# STlinkv21.net
KiCad netlist of a schematic drawn in Altium Designer
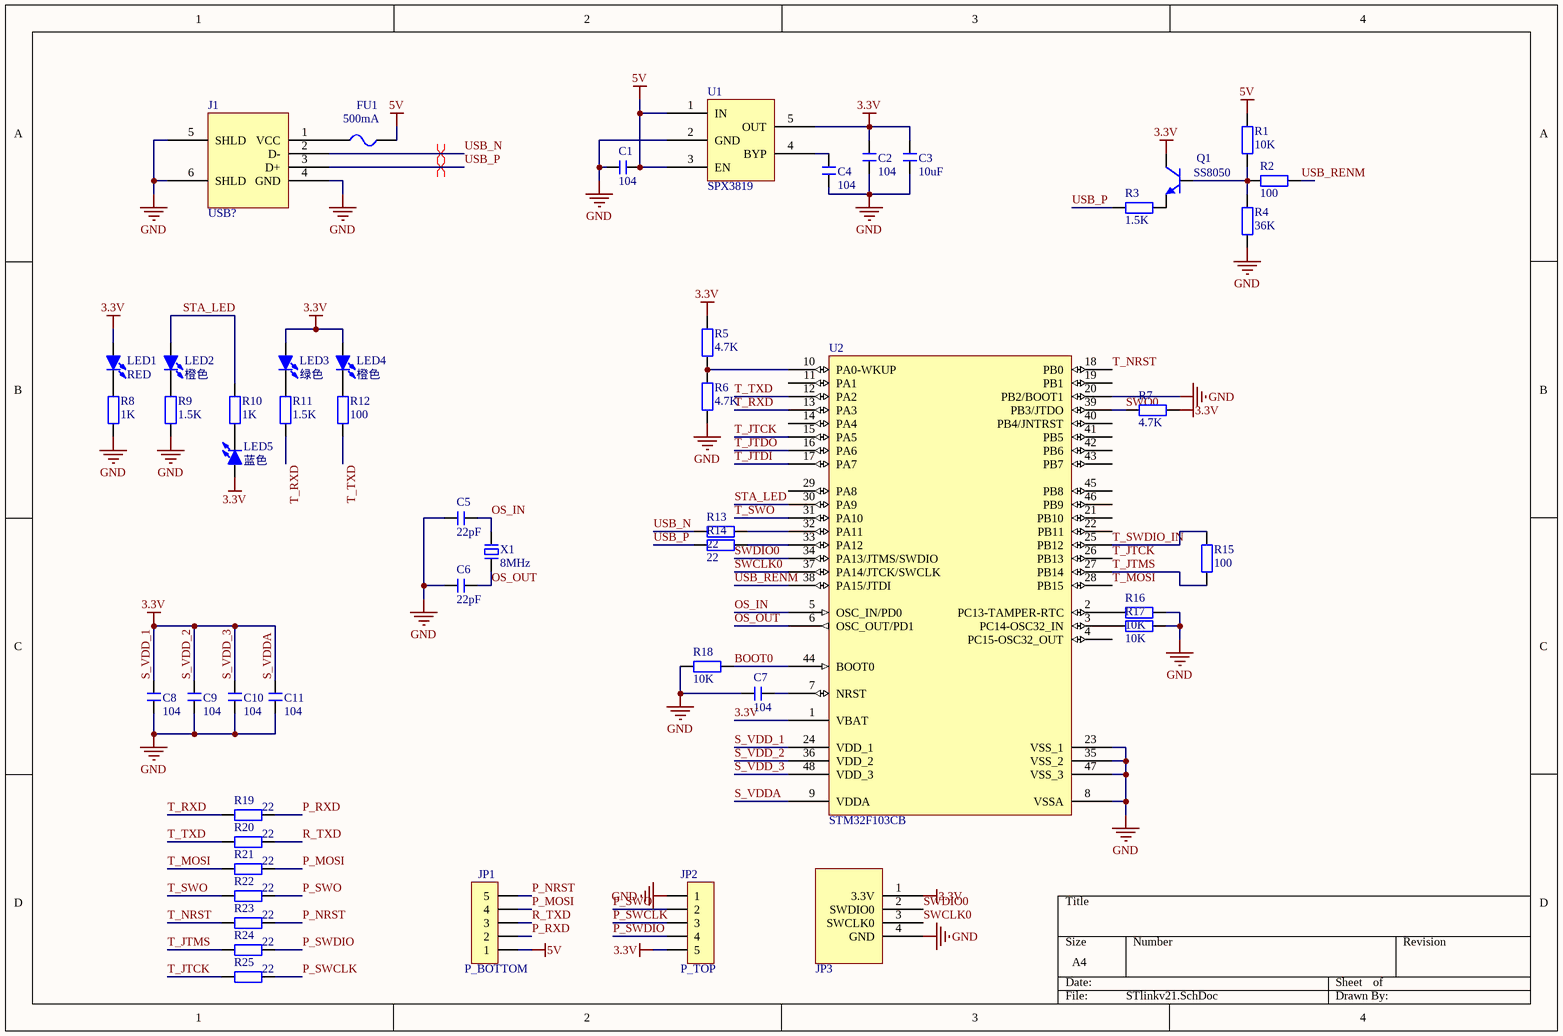
[diagram p0: STlinkv21.SchDoc]

(export (version "E")
  (design (tool "Eeschema 10.0.6"))
  (components
    (comp (ref "*") (value "JP3") (footprint "JP4") (libsource (lib "STlinkv21") (part "JP?")))
    (comp (ref "C1")
      (value "104")
      (footprint "C 0603_L")
      (description "无极性贴片电容")
      (fields (field (name "版权归属") "源创客"))
      (libsource (lib "3.1   - 电阻-电容-电感") (part "C"))
    )
    (comp (ref "C2")
      (value "104")
      (footprint "C 0603_L")
      (description "无极性贴片电容")
      (fields (field (name "版权归属") "源创客"))
      (libsource (lib "3.1   - 电阻-电容-电感") (part "C"))
    )
    (comp (ref "C3")
      (value "10uF")
      (footprint "C 0603_L")
      (description "无极性贴片电容")
      (fields (field (name "版权归属") "源创客"))
      (libsource (lib "3.1   - 电阻-电容-电感") (part "C"))
    )
    (comp (ref "C4")
      (value "104")
      (footprint "C 0603_L")
      (description "无极性贴片电容")
      (fields (field (name "版权归属") "源创客"))
      (libsource (lib "3.1   - 电阻-电容-电感") (part "C"))
    )
    (comp (ref "C5")
      (value "22pF")
      (footprint "C 0603_L")
      (description "无极性贴片电容")
      (fields (field (name "版权归属") "源创客"))
      (libsource (lib "3.1   - 电阻-电容-电感") (part "C"))
    )
    (comp (ref "C6")
      (value "22pF")
      (footprint "C 0603_L")
      (description "无极性贴片电容")
      (fields (field (name "版权归属") "源创客"))
      (libsource (lib "3.1   - 电阻-电容-电感") (part "C"))
    )
    (comp (ref "C7")
      (value "104")
      (footprint "C 0603_L")
      (description "无极性贴片电容")
      (fields (field (name "版权归属") "源创客"))
      (libsource (lib "3.1   - 电阻-电容-电感") (part "C"))
    )
    (comp (ref "C8")
      (value "104")
      (footprint "C 0603_L")
      (description "无极性贴片电容")
      (fields (field (name "版权归属") "源创客"))
      (libsource (lib "3.1   - 电阻-电容-电感") (part "C"))
    )
    (comp (ref "C9")
      (value "104")
      (footprint "C 0603_L")
      (description "无极性贴片电容")
      (fields (field (name "版权归属") "源创客"))
      (libsource (lib "3.1   - 电阻-电容-电感") (part "C"))
    )
    (comp (ref "C10")
      (value "104")
      (footprint "C 0603_L")
      (description "无极性贴片电容")
      (fields (field (name "版权归属") "源创客"))
      (libsource (lib "3.1   - 电阻-电容-电感") (part "C"))
    )
    (comp (ref "C11")
      (value "104")
      (footprint "C 0603_L")
      (description "无极性贴片电容")
      (fields (field (name "版权归属") "源创客"))
      (libsource (lib "3.1   - 电阻-电容-电感") (part "C"))
    )
    (comp (ref "FU1")
      (value "500mA")
      (footprint "FU 0805")
      (description "贴片保险丝")
      (fields (field (name "版权归属") "源创客"))
      (libsource (lib "10.1 - 保险丝-晶振") (part "FU"))
    )
    (comp (ref "J1") (value "USB?") (footprint "USB-A") (libsource (lib "STlinkv21") (part "USB?")))
    (comp (ref "JP1")
      (value "P_BOTTOM")
      (footprint "JP5Bottom")
      (description "5P接插件")
      (fields (field (name "版权归属") "源创客"))
      (libsource (lib "4.5   - 接插件-脚距2.54") (part "Header 5"))
    )
    (comp (ref "JP2")
      (value "P_TOP")
      (footprint "JP5TOP")
      (description "5P接插件")
      (fields (field (name "版权归属") "源创客"))
      (libsource (lib "") (part "Header 5_1"))
    )
    (comp (ref "LED1")
      (value "RED")
      (footprint "LED 0603B")
      (description "贴片LED")
      (fields (field (name "版权归属") "源创客"))
      (libsource (lib "9.1   - LED") (part "LED-SMD"))
    )
    (comp (ref "LED2")
      (value "橙色")
      (footprint "LED 0603B")
      (description "贴片LED")
      (fields (field (name "版权归属") "源创客"))
      (libsource (lib "9.1   - LED") (part "LED-SMD"))
    )
    (comp (ref "LED3")
      (value "绿色")
      (footprint "LED 0603B")
      (description "贴片LED")
      (fields (field (name "版权归属") "源创客"))
      (libsource (lib "9.1   - LED") (part "LED-SMD"))
    )
    (comp (ref "LED4")
      (value "橙色")
      (footprint "LED 0603B")
      (description "贴片LED")
      (fields (field (name "版权归属") "源创客"))
      (libsource (lib "9.1   - LED") (part "LED-SMD"))
    )
    (comp (ref "LED5")
      (value "蓝色")
      (footprint "LED 0603B")
      (description "贴片LED")
      (fields (field (name "版权归属") "源创客"))
      (libsource (lib "9.1   - LED") (part "LED-SMD"))
    )
    (comp (ref "Q1")
      (value "SS8050")
      (footprint "SOT23-3N")
      (description "高频放大-NPN型")
      (fields (field (name "版权归属") "源创客"))
      (libsource (lib "6.2   - 三极管") (part "8050-SMD"))
    )
    (comp (ref "R1")
      (value "10K")
      (footprint "R 0603_L")
      (description "贴片电阻")
      (fields (field (name "版权归属") "源创客"))
      (libsource (lib "3.1   - 电阻-电容-电感") (part "R"))
    )
    (comp (ref "R2")
      (value "100")
      (footprint "R 0603_L")
      (description "贴片电阻")
      (fields (field (name "版权归属") "源创客"))
      (libsource (lib "3.1   - 电阻-电容-电感") (part "R"))
    )
    (comp (ref "R3")
      (value "1.5K")
      (footprint "R 0603_L")
      (description "贴片电阻")
      (fields (field (name "版权归属") "源创客"))
      (libsource (lib "3.1   - 电阻-电容-电感") (part "R"))
    )
    (comp (ref "R4")
      (value "36K")
      (footprint "R 0603_L")
      (description "贴片电阻")
      (fields (field (name "版权归属") "源创客"))
      (libsource (lib "3.1   - 电阻-电容-电感") (part "R"))
    )
    (comp (ref "R5")
      (value "4.7K")
      (footprint "R 0603_L")
      (description "贴片电阻")
      (fields (field (name "版权归属") "源创客"))
      (libsource (lib "3.1   - 电阻-电容-电感") (part "R"))
    )
    (comp (ref "R6")
      (value "4.7K")
      (footprint "R 0603_L")
      (description "贴片电阻")
      (fields (field (name "版权归属") "源创客"))
      (libsource (lib "3.1   - 电阻-电容-电感") (part "R"))
    )
    (comp (ref "R7")
      (value "4.7K")
      (footprint "R 0603_L")
      (description "贴片电阻")
      (fields (field (name "版权归属") "源创客"))
      (libsource (lib "3.1   - 电阻-电容-电感") (part "R"))
    )
    (comp (ref "R8")
      (value "1K")
      (footprint "R 0603_L")
      (description "贴片电阻")
      (fields (field (name "版权归属") "源创客"))
      (libsource (lib "3.1   - 电阻-电容-电感") (part "R"))
    )
    (comp (ref "R9")
      (value "1.5K")
      (footprint "R 0603_L")
      (description "贴片电阻")
      (fields (field (name "版权归属") "源创客"))
      (libsource (lib "3.1   - 电阻-电容-电感") (part "R"))
    )
    (comp (ref "R10")
      (value "1K")
      (footprint "R 0603_L")
      (description "贴片电阻")
      (fields (field (name "版权归属") "源创客"))
      (libsource (lib "3.1   - 电阻-电容-电感") (part "R"))
    )
    (comp (ref "R11")
      (value "1.5K")
      (footprint "R 0603_L")
      (description "贴片电阻")
      (fields (field (name "版权归属") "源创客"))
      (libsource (lib "3.1   - 电阻-电容-电感") (part "R"))
    )
    (comp (ref "R12")
      (value "100")
      (footprint "R 0603_L")
      (description "贴片电阻")
      (fields (field (name "版权归属") "源创客"))
      (libsource (lib "3.1   - 电阻-电容-电感") (part "R"))
    )
    (comp (ref "R13")
      (value "22")
      (footprint "R 0603_L")
      (description "贴片电阻")
      (fields (field (name "版权归属") "源创客"))
      (libsource (lib "3.1   - 电阻-电容-电感") (part "R"))
    )
    (comp (ref "R14")
      (value "22")
      (footprint "R 0603_L")
      (description "贴片电阻")
      (fields (field (name "版权归属") "源创客"))
      (libsource (lib "3.1   - 电阻-电容-电感") (part "R"))
    )
    (comp (ref "R15")
      (value "100")
      (footprint "R 0603_L")
      (description "贴片电阻")
      (fields (field (name "版权归属") "源创客"))
      (libsource (lib "3.1   - 电阻-电容-电感") (part "R"))
    )
    (comp (ref "R16")
      (value "10K")
      (footprint "R 0603_L")
      (description "贴片电阻")
      (fields (field (name "版权归属") "源创客"))
      (libsource (lib "3.1   - 电阻-电容-电感") (part "R"))
    )
    (comp (ref "R17")
      (value "10K")
      (footprint "R 0603_L")
      (description "贴片电阻")
      (fields (field (name "版权归属") "源创客"))
      (libsource (lib "3.1   - 电阻-电容-电感") (part "R"))
    )
    (comp (ref "R18")
      (value "10K")
      (footprint "R 0603_L")
      (description "贴片电阻")
      (fields (field (name "版权归属") "源创客"))
      (libsource (lib "3.1   - 电阻-电容-电感") (part "R"))
    )
    (comp (ref "R19")
      (value "22")
      (footprint "R 0603_L")
      (description "贴片电阻")
      (fields (field (name "版权归属") "源创客"))
      (libsource (lib "3.1   - 电阻-电容-电感") (part "R"))
    )
    (comp (ref "R20")
      (value "22")
      (footprint "R 0603_L")
      (description "贴片电阻")
      (fields (field (name "版权归属") "源创客"))
      (libsource (lib "3.1   - 电阻-电容-电感") (part "R"))
    )
    (comp (ref "R21")
      (value "22")
      (footprint "R 0603_L")
      (description "贴片电阻")
      (fields (field (name "版权归属") "源创客"))
      (libsource (lib "3.1   - 电阻-电容-电感") (part "R"))
    )
    (comp (ref "R22")
      (value "22")
      (footprint "R 0603_L")
      (description "贴片电阻")
      (fields (field (name "版权归属") "源创客"))
      (libsource (lib "3.1   - 电阻-电容-电感") (part "R"))
    )
    (comp (ref "R23")
      (value "22")
      (footprint "R 0603_L")
      (description "贴片电阻")
      (fields (field (name "版权归属") "源创客"))
      (libsource (lib "3.1   - 电阻-电容-电感") (part "R"))
    )
    (comp (ref "R24")
      (value "22")
      (footprint "R 0603_L")
      (description "贴片电阻")
      (fields (field (name "版权归属") "源创客"))
      (libsource (lib "3.1   - 电阻-电容-电感") (part "R"))
    )
    (comp (ref "R25")
      (value "22")
      (footprint "R 0603_L")
      (description "贴片电阻")
      (fields (field (name "版权归属") "源创客"))
      (libsource (lib "3.1   - 电阻-电容-电感") (part "R"))
    )
    (comp (ref "U1") (value "SPX3819") (footprint "SOT-23-5") (libsource (lib "STlinkv21") (part "SPX3819")))
    (comp (ref "U2")
      (value "STM32F103CB")
      (footprint "LQFP48 7X7_L")
      (description "Flaah:64/RAM:20/IO:36")
      (fields (field (name "版权归属") "源创客"))
      (libsource (lib "2.1   - STM32系列单片机") (part "STM32F103C8"))
    )
    (comp (ref "X1")
      (value "8MHz")
      (footprint "OSC 5032-2P")
      (description "2脚无源脚晶振")
      (fields (field (name "版权归属") "源创客"))
      (libsource (lib "10.1 - 保险丝-晶振") (part "XTAL-2P"))
    )
  )
  (nets
    (net (code "1") (name "/BOOT0") (class "Default")
      (node (ref "R18") (pin "1") (pinfunction "1_1") (pintype "passive"))
      (node (ref "U2") (pin "44") (pinfunction "BOOT0_44") (pintype "input"))
    )
    (net (code "2") (name "/OS_IN") (class "Default")
      (node (ref "C5") (pin "2") (pinfunction "2_2") (pintype "passive"))
      (node (ref "U2") (pin "5") (pinfunction "OSC_IN/PD0_5") (pintype "input"))
      (node (ref "X1") (pin "2") (pinfunction "2_2") (pintype "passive"))
    )
    (net (code "3") (name "/OS_OUT") (class "Default")
      (node (ref "C6") (pin "2") (pinfunction "2_2") (pintype "passive"))
      (node (ref "U2") (pin "6") (pinfunction "OSC_OUT/PD1_6") (pintype "output"))
      (node (ref "X1") (pin "1") (pinfunction "1_1") (pintype "passive"))
    )
    (net (code "4") (name "/P_MOSI") (class "Default")
      (node (ref "JP1") (pin "4") (pinfunction "4_4") (pintype "passive"))
      (node (ref "R21") (pin "1") (pinfunction "1_1") (pintype "passive"))
    )
    (net (code "5") (name "/P_NRST") (class "Default")
      (node (ref "JP1") (pin "5") (pinfunction "5_5") (pintype "passive"))
      (node (ref "R23") (pin "1") (pinfunction "1_1") (pintype "passive"))
    )
    (net (code "6") (name "/P_RXD") (class "Default")
      (node (ref "JP1") (pin "2") (pinfunction "2_2") (pintype "passive"))
      (node (ref "R19") (pin "1") (pinfunction "1_1") (pintype "passive"))
    )
    (net (code "7") (name "/P_SWCLK") (class "Default")
      (node (ref "JP2") (pin "3") (pinfunction "3_3") (pintype "passive"))
      (node (ref "R25") (pin "1") (pinfunction "1_1") (pintype "passive"))
    )
    (net (code "8") (name "/P_SWDIO") (class "Default")
      (node (ref "JP2") (pin "4") (pinfunction "4_4") (pintype "passive"))
      (node (ref "R24") (pin "1") (pinfunction "1_1") (pintype "passive"))
    )
    (net (code "9") (name "/P_SWO") (class "Default")
      (node (ref "JP2") (pin "2") (pinfunction "2_2") (pintype "passive"))
      (node (ref "R22") (pin "1") (pinfunction "1_1") (pintype "passive"))
    )
    (net (code "10") (name "/R_TXD") (class "Default")
      (node (ref "JP1") (pin "3") (pinfunction "3_3") (pintype "passive"))
      (node (ref "R20") (pin "1") (pinfunction "1_1") (pintype "passive"))
    )
    (net (code "11") (name "/STA_LED") (class "Default")
      (node (ref "LED2") (pin "1") (pinfunction "A_1") (pintype "passive"))
      (node (ref "R10") (pin "2") (pinfunction "2_2") (pintype "passive"))
      (node (ref "U2") (pin "30") (pinfunction "PA9_30") (pintype "bidirectional"))
    )
    (net (code "12") (name "/SWCLK0") (class "Default")
      (node (ref "*") (pin "3") (pinfunction "SWCLK0_3") (pintype "passive"))
      (node (ref "U2") (pin "37") (pinfunction "PA14/JTCK/SWCLK_37") (pintype "bidirectional"))
    )
    (net (code "13") (name "/SWDIO0") (class "Default")
      (node (ref "*") (pin "2") (pinfunction "SWDIO0_2") (pintype "passive"))
      (node (ref "U2") (pin "34") (pinfunction "PA13/JTMS/SWDIO_34") (pintype "bidirectional"))
    )
    (net (code "14") (name "/SWO0") (class "Default")
      (node (ref "R7") (pin "1") (pinfunction "1_1") (pintype "passive"))
      (node (ref "U2") (pin "39") (pinfunction "PB3/JTDO_39") (pintype "bidirectional"))
    )
    (net (code "15") (name "/T_JTCK") (class "Default")
      (node (ref "R25") (pin "2") (pinfunction "2_2") (pintype "passive"))
      (node (ref "U2") (pin "15") (pinfunction "PA5_15") (pintype "bidirectional"))
      (node (ref "U2") (pin "26") (pinfunction "PB13_26") (pintype "bidirectional"))
    )
    (net (code "16") (name "/T_JTDI") (class "Default")
      (node (ref "U2") (pin "17") (pinfunction "PA7_17") (pintype "bidirectional"))
    )
    (net (code "17") (name "/T_JTDO") (class "Default")
      (node (ref "U2") (pin "16") (pinfunction "PA6_16") (pintype "bidirectional"))
    )
    (net (code "18") (name "/T_JTMS") (class "Default")
      (node (ref "R15") (pin "2") (pinfunction "2_2") (pintype "passive"))
      (node (ref "R24") (pin "2") (pinfunction "2_2") (pintype "passive"))
      (node (ref "U2") (pin "27") (pinfunction "PB14_27") (pintype "bidirectional"))
    )
    (net (code "19") (name "/T_MOSI") (class "Default")
      (node (ref "R21") (pin "2") (pinfunction "2_2") (pintype "passive"))
      (node (ref "U2") (pin "28") (pinfunction "PB15_28") (pintype "bidirectional"))
    )
    (net (code "20") (name "/T_NRST") (class "Default")
      (node (ref "R23") (pin "2") (pinfunction "2_2") (pintype "passive"))
      (node (ref "U2") (pin "18") (pinfunction "PB0_18") (pintype "bidirectional"))
    )
    (net (code "21") (name "/T_RXD") (class "Default")
      (node (ref "R11") (pin "1") (pinfunction "1_1") (pintype "passive"))
      (node (ref "R19") (pin "2") (pinfunction "2_2") (pintype "passive"))
      (node (ref "U2") (pin "13") (pinfunction "PA3_13") (pintype "bidirectional"))
    )
    (net (code "22") (name "/T_SWDIO_IN") (class "Default")
      (node (ref "R15") (pin "1") (pinfunction "1_1") (pintype "passive"))
      (node (ref "U2") (pin "25") (pinfunction "PB12_25") (pintype "bidirectional"))
    )
    (net (code "23") (name "/T_SWO") (class "Default")
      (node (ref "R22") (pin "2") (pinfunction "2_2") (pintype "passive"))
      (node (ref "U2") (pin "31") (pinfunction "PA10_31") (pintype "bidirectional"))
    )
    (net (code "24") (name "/T_TXD") (class "Default")
      (node (ref "R12") (pin "1") (pinfunction "1_1") (pintype "passive"))
      (node (ref "R20") (pin "2") (pinfunction "2_2") (pintype "passive"))
      (node (ref "U2") (pin "12") (pinfunction "PA2_12") (pintype "bidirectional"))
    )
    (net (code "25") (name "/USB_N") (class "Default")
      (node (ref "J1") (pin "2") (pinfunction "D-_2") (pintype "passive"))
      (node (ref "R13") (pin "2") (pinfunction "2_2") (pintype "passive"))
    )
    (net (code "26") (name "/USB_P") (class "Default")
      (node (ref "J1") (pin "3") (pinfunction "D+_3") (pintype "passive"))
      (node (ref "R14") (pin "2") (pinfunction "2_2") (pintype "passive"))
      (node (ref "R3") (pin "1") (pinfunction "1_1") (pintype "passive"))
    )
    (net (code "27") (name "/USB_RENM") (class "Default")
      (node (ref "R2") (pin "2") (pinfunction "2_2") (pintype "passive"))
      (node (ref "U2") (pin "38") (pinfunction "PA15/JTDI_38") (pintype "bidirectional"))
    )
    (net (code "28") (name "3.3V") (class "Default")
      (node (ref "*") (pin "1") (pinfunction "3.3V_1") (pintype "passive"))
      (node (ref "C10") (pin "2") (pinfunction "2_2") (pintype "passive"))
      (node (ref "C11") (pin "2") (pinfunction "2_2") (pintype "passive"))
      (node (ref "C2") (pin "2") (pinfunction "2_2") (pintype "passive"))
      (node (ref "C3") (pin "2") (pinfunction "2_2") (pintype "passive"))
      (node (ref "C8") (pin "2") (pinfunction "2_2") (pintype "passive"))
      (node (ref "C9") (pin "2") (pinfunction "2_2") (pintype "passive"))
      (node (ref "JP2") (pin "5") (pinfunction "5_5") (pintype "passive"))
      (node (ref "LED1") (pin "1") (pinfunction "A_1") (pintype "passive"))
      (node (ref "LED3") (pin "1") (pinfunction "A_1") (pintype "passive"))
      (node (ref "LED4") (pin "1") (pinfunction "A_1") (pintype "passive"))
      (node (ref "LED5") (pin "1") (pinfunction "A_1") (pintype "passive"))
      (node (ref "Q1") (pin "3") (pinfunction "C_3") (pintype "passive"))
      (node (ref "R5") (pin "2") (pinfunction "2_2") (pintype "passive"))
      (node (ref "R7") (pin "2") (pinfunction "2_2") (pintype "passive"))
      (node (ref "U1") (pin "5") (pinfunction "OUT_5") (pintype "passive"))
      (node (ref "U2") (pin "1") (pinfunction "VBAT_1") (pintype "power_in"))
      (node (ref "U2") (pin "24") (pinfunction "VDD_1_24") (pintype "power_in"))
      (node (ref "U2") (pin "36") (pinfunction "VDD_2_36") (pintype "power_in"))
      (node (ref "U2") (pin "48") (pinfunction "VDD_3_48") (pintype "power_in"))
      (node (ref "U2") (pin "9") (pinfunction "VDDA_9") (pintype "power_in"))
    )
    (net (code "29") (name "5V") (class "Default")
      (node (ref "C1") (pin "2") (pinfunction "2_2") (pintype "passive"))
      (node (ref "FU1") (pin "2") (pinfunction "2_2") (pintype "passive"))
      (node (ref "JP1") (pin "1") (pinfunction "1_1") (pintype "passive"))
      (node (ref "R1") (pin "2") (pinfunction "2_2") (pintype "passive"))
      (node (ref "U1") (pin "1") (pinfunction "IN_1") (pintype "passive"))
      (node (ref "U1") (pin "3") (pinfunction "EN_3") (pintype "passive"))
    )
    (net (code "30") (name "GND") (class "Default")
      (node (ref "*") (pin "4") (pinfunction "GND_4") (pintype "passive"))
      (node (ref "C1") (pin "1") (pinfunction "1_1") (pintype "passive"))
      (node (ref "C10") (pin "1") (pinfunction "1_1") (pintype "passive"))
      (node (ref "C11") (pin "1") (pinfunction "1_1") (pintype "passive"))
      (node (ref "C2") (pin "1") (pinfunction "1_1") (pintype "passive"))
      (node (ref "C3") (pin "1") (pinfunction "1_1") (pintype "passive"))
      (node (ref "C4") (pin "1") (pinfunction "1_1") (pintype "passive"))
      (node (ref "C5") (pin "1") (pinfunction "1_1") (pintype "passive"))
      (node (ref "C6") (pin "1") (pinfunction "1_1") (pintype "passive"))
      (node (ref "C7") (pin "1") (pinfunction "1_1") (pintype "passive"))
      (node (ref "C8") (pin "1") (pinfunction "1_1") (pintype "passive"))
      (node (ref "C9") (pin "1") (pinfunction "1_1") (pintype "passive"))
      (node (ref "J1") (pin "4") (pinfunction "GND_4") (pintype "passive"))
      (node (ref "J1") (pin "5") (pinfunction "SHLD_5") (pintype "passive"))
      (node (ref "J1") (pin "6") (pinfunction "SHLD_6") (pintype "passive"))
      (node (ref "JP2") (pin "1") (pinfunction "1_1") (pintype "passive"))
      (node (ref "R16") (pin "1") (pinfunction "1_1") (pintype "passive"))
      (node (ref "R17") (pin "1") (pinfunction "1_1") (pintype "passive"))
      (node (ref "R18") (pin "2") (pinfunction "2_2") (pintype "passive"))
      (node (ref "R4") (pin "1") (pinfunction "1_1") (pintype "passive"))
      (node (ref "R6") (pin "1") (pinfunction "1_1") (pintype "passive"))
      (node (ref "R8") (pin "1") (pinfunction "1_1") (pintype "passive"))
      (node (ref "R9") (pin "1") (pinfunction "1_1") (pintype "passive"))
      (node (ref "U1") (pin "2") (pinfunction "GND_2") (pintype "passive"))
      (node (ref "U2") (pin "20") (pinfunction "PB2/BOOT1_20") (pintype "bidirectional"))
      (node (ref "U2") (pin "23") (pinfunction "VSS_1_23") (pintype "power_in"))
      (node (ref "U2") (pin "35") (pinfunction "VSS_2_35") (pintype "power_in"))
      (node (ref "U2") (pin "47") (pinfunction "VSS_3_47") (pintype "power_in"))
      (node (ref "U2") (pin "8") (pinfunction "VSSA_8") (pintype "power_in"))
    )
    (net (code "31") (name "Net-(J1-VCC)") (class "Default")
      (node (ref "FU1") (pin "1") (pinfunction "1_1") (pintype "passive"))
      (node (ref "J1") (pin "1") (pinfunction "VCC_1") (pintype "passive"))
    )
    (net (code "32") (name "Net-(LED1-K)") (class "Default")
      (node (ref "LED1") (pin "2") (pinfunction "K_2") (pintype "passive"))
      (node (ref "R8") (pin "2") (pinfunction "2_2") (pintype "passive"))
    )
    (net (code "33") (name "Net-(LED2-K)") (class "Default")
      (node (ref "LED2") (pin "2") (pinfunction "K_2") (pintype "passive"))
      (node (ref "R9") (pin "2") (pinfunction "2_2") (pintype "passive"))
    )
    (net (code "34") (name "Net-(LED3-K)") (class "Default")
      (node (ref "LED3") (pin "2") (pinfunction "K_2") (pintype "passive"))
      (node (ref "R11") (pin "2") (pinfunction "2_2") (pintype "passive"))
    )
    (net (code "35") (name "Net-(LED4-K)") (class "Default")
      (node (ref "LED4") (pin "2") (pinfunction "K_2") (pintype "passive"))
      (node (ref "R12") (pin "2") (pinfunction "2_2") (pintype "passive"))
    )
    (net (code "36") (name "Net-(LED5-K)") (class "Default")
      (node (ref "LED5") (pin "2") (pinfunction "K_2") (pintype "passive"))
      (node (ref "R10") (pin "1") (pinfunction "1_1") (pintype "passive"))
    )
    (net (code "37") (name "Net-(Q1-B)") (class "Default")
      (node (ref "Q1") (pin "1") (pinfunction "B_1") (pintype "passive"))
      (node (ref "R1") (pin "1") (pinfunction "1_1") (pintype "passive"))
      (node (ref "R2") (pin "1") (pinfunction "1_1") (pintype "passive"))
      (node (ref "R4") (pin "2") (pinfunction "2_2") (pintype "passive"))
    )
    (net (code "38") (name "Net-(Q1-E)") (class "Default")
      (node (ref "Q1") (pin "2") (pinfunction "E_2") (pintype "passive"))
      (node (ref "R3") (pin "2") (pinfunction "2_2") (pintype "passive"))
    )
    (net (code "39") (name "Net-(U1-BYP)") (class "Default")
      (node (ref "C4") (pin "2") (pinfunction "2_2") (pintype "passive"))
      (node (ref "U1") (pin "4") (pinfunction "BYP_4") (pintype "passive"))
    )
    (net (code "40") (name "Net-(U2-NRST)") (class "Default")
      (node (ref "C7") (pin "2") (pinfunction "2_2") (pintype "passive"))
      (node (ref "U2") (pin "7") (pinfunction "NRST_7") (pintype "bidirectional"))
    )
    (net (code "41") (name "Net-(U2-PA0-WKUP)") (class "Default")
      (node (ref "R5") (pin "1") (pinfunction "1_1") (pintype "passive"))
      (node (ref "R6") (pin "2") (pinfunction "2_2") (pintype "passive"))
      (node (ref "U2") (pin "10") (pinfunction "PA0-WKUP_10") (pintype "bidirectional"))
    )
    (net (code "42") (name "Net-(U2-PA11)") (class "Default")
      (node (ref "R13") (pin "1") (pinfunction "1_1") (pintype "passive"))
      (node (ref "U2") (pin "32") (pinfunction "PA11_32") (pintype "bidirectional"))
    )
    (net (code "43") (name "Net-(U2-PA12)") (class "Default")
      (node (ref "R14") (pin "1") (pinfunction "1_1") (pintype "passive"))
      (node (ref "U2") (pin "33") (pinfunction "PA12_33") (pintype "bidirectional"))
    )
    (net (code "44") (name "Net-(U2-PC13-TAMPER-RTC)") (class "Default")
      (node (ref "R16") (pin "2") (pinfunction "2_2") (pintype "passive"))
      (node (ref "U2") (pin "2") (pinfunction "PC13-TAMPER-RTC_2") (pintype "bidirectional"))
    )
    (net (code "45") (name "Net-(U2-PC14-OSC32_IN)") (class "Default")
      (node (ref "R17") (pin "2") (pinfunction "2_2") (pintype "passive"))
      (node (ref "U2") (pin "3") (pinfunction "PC14-OSC32_IN_3") (pintype "bidirectional"))
    )
    (net (code "46") (name "unconnected-(U2-PA1-Pad11)") (class "Default")
      (node (ref "U2") (pin "11") (pinfunction "PA1_11") (pintype "bidirectional"))
    )
    (net (code "47") (name "unconnected-(U2-PA4-Pad14)") (class "Default")
      (node (ref "U2") (pin "14") (pinfunction "PA4_14") (pintype "bidirectional"))
    )
    (net (code "48") (name "unconnected-(U2-PA8-Pad29)") (class "Default")
      (node (ref "U2") (pin "29") (pinfunction "PA8_29") (pintype "bidirectional"))
    )
    (net (code "49") (name "unconnected-(U2-PB1-Pad19)") (class "Default")
      (node (ref "U2") (pin "19") (pinfunction "PB1_19") (pintype "bidirectional"))
    )
    (net (code "50") (name "unconnected-(U2-PB4{slash}JNTRST-Pad40)") (class "Default")
      (node (ref "U2") (pin "40") (pinfunction "PB4/JNTRST_40") (pintype "bidirectional"))
    )
    (net (code "51") (name "unconnected-(U2-PB5-Pad41)") (class "Default")
      (node (ref "U2") (pin "41") (pinfunction "PB5_41") (pintype "bidirectional"))
    )
    (net (code "52") (name "unconnected-(U2-PB6-Pad42)") (class "Default")
      (node (ref "U2") (pin "42") (pinfunction "PB6_42") (pintype "bidirectional"))
    )
    (net (code "53") (name "unconnected-(U2-PB7-Pad43)") (class "Default")
      (node (ref "U2") (pin "43") (pinfunction "PB7_43") (pintype "bidirectional"))
    )
    (net (code "54") (name "unconnected-(U2-PB8-Pad45)") (class "Default")
      (node (ref "U2") (pin "45") (pinfunction "PB8_45") (pintype "bidirectional"))
    )
    (net (code "55") (name "unconnected-(U2-PB9-Pad46)") (class "Default")
      (node (ref "U2") (pin "46") (pinfunction "PB9_46") (pintype "bidirectional"))
    )
    (net (code "56") (name "unconnected-(U2-PB10-Pad21)") (class "Default")
      (node (ref "U2") (pin "21") (pinfunction "PB10_21") (pintype "bidirectional"))
    )
    (net (code "57") (name "unconnected-(U2-PB11-Pad22)") (class "Default")
      (node (ref "U2") (pin "22") (pinfunction "PB11_22") (pintype "bidirectional"))
    )
    (net (code "58") (name "unconnected-(U2-PC15-OSC32_OUT-Pad4)") (class "Default")
      (node (ref "U2") (pin "4") (pinfunction "PC15-OSC32_OUT_4") (pintype "bidirectional"))
    )
  )
)
